# WakeOverWlan.net
KiCad netlist of a schematic drawn in EAGLE
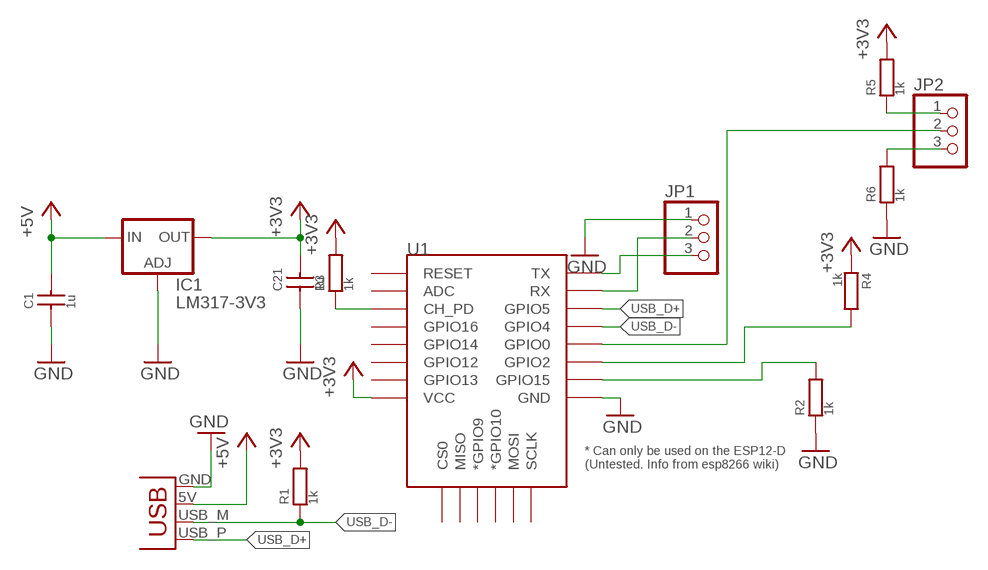
[diagram p0: schematic, sheet 1]

(export (version "E")
  (design (tool "Eeschema 10.0.6"))
  (components
    (comp (ref "C1")
      (value "1u")
      (footprint "eagle-import:C0805")
      (libsource (lib "eagle-import") (part "C_SMD0805"))
    )
    (comp (ref "C21")
      (value "1u")
      (footprint "eagle-import:C0805")
      (libsource (lib "eagle-import") (part "C_SMD0805"))
    )
    (comp (ref "IC1")
      (value "LM317-3V3")
      (footprint "eagle-import:SOT223")
      (libsource (lib "eagle-import") (part "LM317?MBSTT3"))
    )
    (comp (ref "JP1")
      (value "PINHD-1X3")
      (footprint "eagle-import:1X03")
      (libsource (lib "eagle-import") (part "PINHD-1X3"))
    )
    (comp (ref "JP2")
      (value "PINHD-1X3")
      (footprint "eagle-import:1X03")
      (libsource (lib "eagle-import") (part "PINHD-1X3"))
    )
    (comp (ref "R1")
      (value "1k")
      (footprint "eagle-import:R0603")
      (libsource (lib "eagle-import") (part "R0603"))
    )
    (comp (ref "R2")
      (value "1k")
      (footprint "eagle-import:R0603")
      (libsource (lib "eagle-import") (part "R0603"))
    )
    (comp (ref "R3")
      (value "1k")
      (footprint "eagle-import:R0603")
      (libsource (lib "eagle-import") (part "R0603"))
    )
    (comp (ref "R4")
      (value "1k")
      (footprint "eagle-import:R0603")
      (libsource (lib "eagle-import") (part "R0603"))
    )
    (comp (ref "R5")
      (value "1k")
      (footprint "eagle-import:R0603")
      (libsource (lib "eagle-import") (part "R0603"))
    )
    (comp (ref "R6")
      (value "1k")
      (footprint "eagle-import:R0603")
      (libsource (lib "eagle-import") (part "R0603"))
    )
    (comp (ref "U1")
      (value "ESP12ESMD")
      (footprint "eagle-import:ESP12E-SMD")
      (libsource (lib "eagle-import") (part "ESP12ESMD"))
    )
    (comp (ref "X1")
      (value "USBPCB")
      (footprint "eagle-import:USB-A-PCB")
      (libsource (lib "eagle-import") (part "USBPCB"))
    )
  )
  (nets
    (net (code "1") (name "+3V3") (class "Default")
      (node (ref "C21") (pin "2") (pinfunction "P$2_2") (pintype "passive"))
      (node (ref "IC1") (pin "4") (pinfunction "OUT_4") (pintype "passive"))
      (node (ref "R1") (pin "2") (pinfunction "P$2_2") (pintype "passive"))
      (node (ref "R3") (pin "2") (pinfunction "P$2_2") (pintype "passive"))
      (node (ref "R4") (pin "1") (pinfunction "P$1_1") (pintype "passive"))
      (node (ref "R5") (pin "2") (pinfunction "P$2_2") (pintype "passive"))
      (node (ref "U1") (pin "VCC") (pinfunction "VCC_VCC") (pintype "bidirectional"))
    )
    (net (code "2") (name "+5V") (class "Default")
      (node (ref "C1") (pin "2") (pinfunction "P$2_2") (pintype "passive"))
      (node (ref "IC1") (pin "3") (pinfunction "IN_3") (pintype "input"))
      (node (ref "X1") (pin "5V") (pinfunction "VBUS_5V") (pintype "bidirectional"))
    )
    (net (code "3") (name "GND") (class "Default")
      (node (ref "C1") (pin "1") (pinfunction "P$1_1") (pintype "passive"))
      (node (ref "C21") (pin "1") (pinfunction "P$1_1") (pintype "passive"))
      (node (ref "IC1") (pin "1") (pinfunction "ADJ_1") (pintype "input"))
      (node (ref "JP1") (pin "1") (pinfunction "1_1") (pintype "passive"))
      (node (ref "R2") (pin "1") (pinfunction "P$1_1") (pintype "passive"))
      (node (ref "R6") (pin "1") (pinfunction "P$1_1") (pintype "passive"))
      (node (ref "U1") (pin "GND") (pinfunction "GND_GND") (pintype "bidirectional"))
      (node (ref "X1") (pin "GND") (pinfunction "GND_GND") (pintype "bidirectional"))
    )
    (net (code "4") (name "Net-(JP2-Pad2)") (class "Default")
      (node (ref "JP2") (pin "2") (pinfunction "2_2") (pintype "passive"))
      (node (ref "U1") (pin "GPIO0") (pinfunction "GPIO0_GPIO0") (pintype "bidirectional"))
    )
    (net (code "5") (name "Net-(R2-P$2)") (class "Default")
      (node (ref "R2") (pin "2") (pinfunction "P$2_2") (pintype "passive"))
      (node (ref "U1") (pin "GPIO15") (pinfunction "GPIO15_GPIO15") (pintype "bidirectional"))
    )
    (net (code "6") (name "Net-(R3-P$1)") (class "Default")
      (node (ref "R3") (pin "1") (pinfunction "P$1_1") (pintype "passive"))
      (node (ref "U1") (pin "CH_PD") (pinfunction "CH_PD_CH_PD") (pintype "bidirectional"))
    )
    (net (code "7") (name "Net-(R4-P$2)") (class "Default")
      (node (ref "R4") (pin "2") (pinfunction "P$2_2") (pintype "passive"))
      (node (ref "U1") (pin "GPIO2") (pinfunction "GPIO2_GPIO2") (pintype "bidirectional"))
    )
    (net (code "8") (name "Net-(R5-P$1)") (class "Default")
      (node (ref "JP2") (pin "1") (pinfunction "1_1") (pintype "passive"))
      (node (ref "R5") (pin "1") (pinfunction "P$1_1") (pintype "passive"))
    )
    (net (code "9") (name "Net-(R6-P$2)") (class "Default")
      (node (ref "JP2") (pin "3") (pinfunction "3_3") (pintype "passive"))
      (node (ref "R6") (pin "2") (pinfunction "P$2_2") (pintype "passive"))
    )
    (net (code "10") (name "Net-(U1-RX)") (class "Default")
      (node (ref "JP1") (pin "2") (pinfunction "2_2") (pintype "passive"))
      (node (ref "U1") (pin "RXD0") (pinfunction "RX_RXD0") (pintype "bidirectional"))
    )
    (net (code "11") (name "Net-(U1-TX)") (class "Default")
      (node (ref "JP1") (pin "3") (pinfunction "3_3") (pintype "passive"))
      (node (ref "U1") (pin "TXD0") (pinfunction "TX_TXD0") (pintype "bidirectional"))
    )
    (net (code "12") (name "USB_D+") (class "Default")
      (node (ref "U1") (pin "GPIO5") (pinfunction "GPIO5_GPIO5") (pintype "bidirectional"))
      (node (ref "X1") (pin "USB_P") (pinfunction "D+_USB_P") (pintype "bidirectional"))
    )
    (net (code "13") (name "USB_D-") (class "Default")
      (node (ref "R1") (pin "1") (pinfunction "P$1_1") (pintype "passive"))
      (node (ref "U1") (pin "GPIO4") (pinfunction "GPIO4_GPIO4") (pintype "bidirectional"))
      (node (ref "X1") (pin "USB_M") (pinfunction "D-_USB_M") (pintype "bidirectional"))
    )
    (net (code "14") (name "unconnected-(U1-*GPIO9-PadGPIO9)") (class "Default")
      (node (ref "U1") (pin "GPIO9") (pinfunction "*GPIO9_GPIO9") (pintype "bidirectional"))
    )
    (net (code "15") (name "unconnected-(U1-*GPIO10-PadGPIO10)") (class "Default")
      (node (ref "U1") (pin "GPIO10") (pinfunction "*GPIO10_GPIO10") (pintype "bidirectional"))
    )
    (net (code "16") (name "unconnected-(U1-PadADC)") (class "Default")
      (node (ref "U1") (pin "ADC") (pinfunction "ADC_ADC") (pintype "bidirectional"))
    )
    (net (code "17") (name "unconnected-(U1-PadCS0)") (class "Default")
      (node (ref "U1") (pin "CS0") (pinfunction "CS0_CS0") (pintype "bidirectional"))
    )
    (net (code "18") (name "unconnected-(U1-PadGPIO12)") (class "Default")
      (node (ref "U1") (pin "GPIO12") (pinfunction "GPIO12_GPIO12") (pintype "bidirectional"))
    )
    (net (code "19") (name "unconnected-(U1-PadGPIO13)") (class "Default")
      (node (ref "U1") (pin "GPIO13") (pinfunction "GPIO13_GPIO13") (pintype "bidirectional"))
    )
    (net (code "20") (name "unconnected-(U1-PadGPIO14)") (class "Default")
      (node (ref "U1") (pin "GPIO14") (pinfunction "GPIO14_GPIO14") (pintype "bidirectional"))
    )
    (net (code "21") (name "unconnected-(U1-PadGPIO16)") (class "Default")
      (node (ref "U1") (pin "GPIO16") (pinfunction "GPIO16_GPIO16") (pintype "bidirectional"))
    )
    (net (code "22") (name "unconnected-(U1-PadMISO)") (class "Default")
      (node (ref "U1") (pin "MISO") (pinfunction "MISO_MISO") (pintype "bidirectional"))
    )
    (net (code "23") (name "unconnected-(U1-PadMOSI)") (class "Default")
      (node (ref "U1") (pin "MOSI") (pinfunction "MOSI_MOSI") (pintype "bidirectional"))
    )
    (net (code "24") (name "unconnected-(U1-PadRESET)") (class "Default")
      (node (ref "U1") (pin "RESET") (pinfunction "RESET_RESET") (pintype "bidirectional"))
    )
    (net (code "25") (name "unconnected-(U1-PadSCLK)") (class "Default")
      (node (ref "U1") (pin "SCLK") (pinfunction "SCLK_SCLK") (pintype "bidirectional"))
    )
  )
)
